# SDtop.net
KiCad netlist of a schematic drawn in Altium Designer
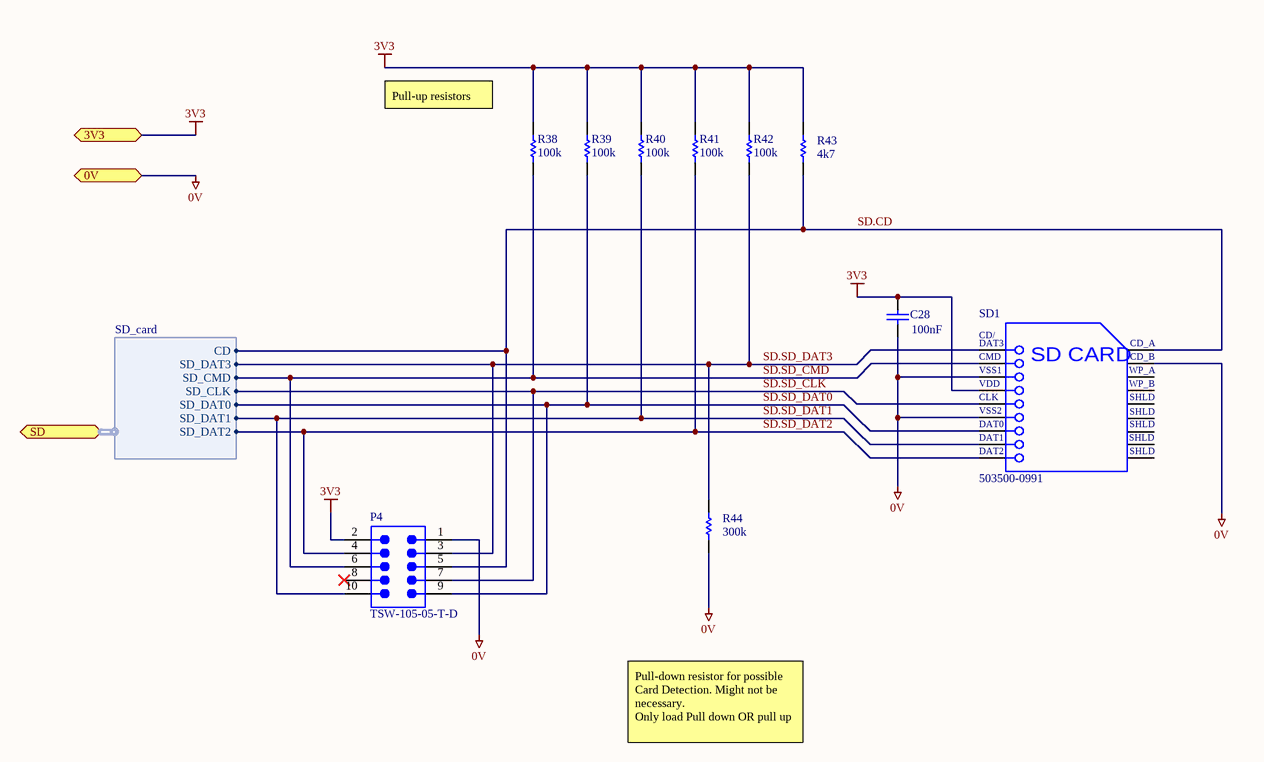
[diagram p0: SDtop.SchDoc]

(export (version "E")
  (design (tool "Eeschema 10.0.6"))
  (components
    (comp (ref "C28")
      (value "100nF")
      (footprint "CAPC0603(1608)100_M")
      (description "CAP 100nF 16V ±5% 0603 (1608 Metric) Thickness 1mm SMD")
      (fields (field (name "TOLERANCE") "Â±5%") (field (name "Comment") "CAP 100nF 16V 0603(1608)"))
      (libsource (lib "Altium Content Vault") (part "CMP-1035-02583-1"))
    )
    (comp (ref "P4")
      (value "TSW-105-05-T-D")
      (footprint "SMTC-TSW-105-05-X-D")
      (fields (field (name "MANUFACTURER") "Samtec"))
      (libsource (lib "Altium Content Vault") (part "SMTC-TSW-105-X-X-D-X"))
    )
    (comp (ref "R38")
      (value "100k")
      (footprint "RESC0603(1608)_N")
      (description "100K 0.1W 1% 0603 (1608 Metric)  SMD")
      (fields (field (name "POWER") "0.1 W") (field (name "TOLERANCE") "1 %"))
      (libsource (lib "Altium Content Vault") (part "CMP-1012-00736-1"))
    )
    (comp (ref "R39")
      (value "100k")
      (footprint "RESC0603(1608)_N")
      (description "100K 0.1W 1% 0603 (1608 Metric)  SMD")
      (fields (field (name "POWER") "0.1 W") (field (name "TOLERANCE") "1 %"))
      (libsource (lib "Altium Content Vault") (part "CMP-1012-00736-1"))
    )
    (comp (ref "R40")
      (value "100k")
      (footprint "RESC0603(1608)_N")
      (description "100K 0.1W 1% 0603 (1608 Metric)  SMD")
      (fields (field (name "POWER") "0.1 W") (field (name "TOLERANCE") "1 %"))
      (libsource (lib "Altium Content Vault") (part "CMP-1012-00736-1"))
    )
    (comp (ref "R41")
      (value "100k")
      (footprint "RESC0603(1608)_N")
      (description "100K 0.1W 1% 0603 (1608 Metric)  SMD")
      (fields (field (name "POWER") "0.1 W") (field (name "TOLERANCE") "1 %"))
      (libsource (lib "Altium Content Vault") (part "CMP-1012-00736-1"))
    )
    (comp (ref "R42")
      (value "100k")
      (footprint "RESC0603(1608)_N")
      (description "100K 0.1W 1% 0603 (1608 Metric)  SMD")
      (fields (field (name "POWER") "0.1 W") (field (name "TOLERANCE") "1 %"))
      (libsource (lib "Altium Content Vault") (part "CMP-1012-00736-1"))
    )
    (comp (ref "R43")
      (value "4k7")
      (footprint "RESC0603(1608)_N")
      (description "4K7 0.1W 1% 0603 (1608 Metric)  SMD")
      (fields (field (name "POWER") "0.1 W") (field (name "TOLERANCE") "1 %"))
      (libsource (lib "Altium Content Vault") (part "CMP-1012-00586-1"))
    )
    (comp (ref "R44")
      (value "300k")
      (footprint "RESC0603(1608)_M")
      (description "300K 0.1W 1% 0603 (1608 Metric)  SMD")
      (fields (field (name "POWER") "0.1 W") (field (name "TOLERANCE") "1 %"))
      (libsource (lib "Altium Content Vault") (part "CMP-1012-00788-1"))
    )
    (comp (ref "SD1")
      (value "503500-0991")
      (footprint "MOLX-503500-0991_V")
      (description "SD and Combo Memory Card Connector, 9 Position Surface Mount, -25 to 85 degC, RoHS, Tape and Reel")
      (libsource (lib "Altium Content Vault") (part "CMP-1676-00006-1"))
    )
  )
  (nets
    (net (code "2") (name "/SD.CD") (class "Default")
      (node (ref "P4") (pin "5") (pinfunction "5_5") (pintype "passive"))
      (node (ref "R43") (pin "1") (pinfunction "1_1") (pintype "passive"))
      (node (ref "SD1") (pin "10") (pinfunction "CD_A_10") (pintype "passive"))
    )
    (net (code "3") (name "/SD.SD_CLK") (class "Default")
      (node (ref "P4") (pin "7") (pinfunction "7_7") (pintype "passive"))
      (node (ref "SD1") (pin "5") (pinfunction "CLK_5") (pintype "passive"))
    )
    (net (code "4") (name "/SD.SD_CMD") (class "Default")
      (node (ref "P4") (pin "6") (pinfunction "6_6") (pintype "passive"))
      (node (ref "R38") (pin "1") (pinfunction "1_1") (pintype "passive"))
      (node (ref "SD1") (pin "2") (pinfunction "CMD_2") (pintype "passive"))
    )
    (net (code "5") (name "/SD.SD_DAT0") (class "Default")
      (node (ref "P4") (pin "9") (pinfunction "9_9") (pintype "passive"))
      (node (ref "R39") (pin "1") (pinfunction "1_1") (pintype "passive"))
      (node (ref "SD1") (pin "7") (pinfunction "DAT0_7") (pintype "passive"))
    )
    (net (code "6") (name "/SD.SD_DAT1") (class "Default")
      (node (ref "P4") (pin "10") (pinfunction "10_10") (pintype "passive"))
      (node (ref "R40") (pin "1") (pinfunction "1_1") (pintype "passive"))
      (node (ref "SD1") (pin "8") (pinfunction "DAT1_8") (pintype "passive"))
    )
    (net (code "7") (name "/SD.SD_DAT2") (class "Default")
      (node (ref "P4") (pin "4") (pinfunction "4_4") (pintype "passive"))
      (node (ref "R41") (pin "1") (pinfunction "1_1") (pintype "passive"))
      (node (ref "SD1") (pin "9") (pinfunction "DAT2_9") (pintype "passive"))
    )
    (net (code "8") (name "/SD.SD_DAT3") (class "Default")
      (node (ref "P4") (pin "3") (pinfunction "3_3") (pintype "passive"))
      (node (ref "R42") (pin "1") (pinfunction "1_1") (pintype "passive"))
      (node (ref "R44") (pin "2") (pinfunction "2_2") (pintype "passive"))
      (node (ref "SD1") (pin "1") (pinfunction "CD/DAT3_1") (pintype "passive"))
    )
    (net (code "10") (name "0V") (class "Default")
      (node (ref "C28") (pin "1") (pinfunction "1_1") (pintype "passive"))
      (node (ref "P4") (pin "1") (pinfunction "1_1") (pintype "passive"))
      (node (ref "R44") (pin "1") (pinfunction "1_1") (pintype "passive"))
      (node (ref "SD1") (pin "11") (pinfunction "CD_B_11") (pintype "passive"))
      (node (ref "SD1") (pin "3") (pinfunction "VSS1_3") (pintype "passive"))
      (node (ref "SD1") (pin "6") (pinfunction "VSS2_6") (pintype "passive"))
    )
    (net (code "11") (name "3V3") (class "Default")
      (node (ref "C28") (pin "2") (pinfunction "2_2") (pintype "passive"))
      (node (ref "P4") (pin "2") (pinfunction "2_2") (pintype "passive"))
      (node (ref "R38") (pin "2") (pinfunction "2_2") (pintype "passive"))
      (node (ref "R39") (pin "2") (pinfunction "2_2") (pintype "passive"))
      (node (ref "R40") (pin "2") (pinfunction "2_2") (pintype "passive"))
      (node (ref "R41") (pin "2") (pinfunction "2_2") (pintype "passive"))
      (node (ref "R42") (pin "2") (pinfunction "2_2") (pintype "passive"))
      (node (ref "R43") (pin "2") (pinfunction "2_2") (pintype "passive"))
      (node (ref "SD1") (pin "4") (pinfunction "VDD_4") (pintype "passive"))
    )
    (net (code "12") (name "unconnected-(P4-Pad8)") (class "Default")
      (node (ref "P4") (pin "8") (pinfunction "8_8") (pintype "passive+no_connect"))
    )
    (net (code "13") (name "unconnected-(SD1-SHLD1-Pad14)") (class "Default")
      (node (ref "SD1") (pin "14") (pinfunction "SHLD1_14") (pintype "passive"))
    )
    (net (code "14") (name "unconnected-(SD1-SHLD2-Pad15)") (class "Default")
      (node (ref "SD1") (pin "15") (pinfunction "SHLD2_15") (pintype "passive"))
    )
    (net (code "15") (name "unconnected-(SD1-SHLD3-Pad16)") (class "Default")
      (node (ref "SD1") (pin "16") (pinfunction "SHLD3_16") (pintype "passive"))
    )
    (net (code "16") (name "unconnected-(SD1-SHLD4-Pad17)") (class "Default")
      (node (ref "SD1") (pin "17") (pinfunction "SHLD4_17") (pintype "passive"))
    )
    (net (code "17") (name "unconnected-(SD1-SHLD5-Pad18)") (class "Default")
      (node (ref "SD1") (pin "18") (pinfunction "SHLD5_18") (pintype "passive"))
    )
    (net (code "18") (name "unconnected-(SD1-WP_A-Pad12)") (class "Default")
      (node (ref "SD1") (pin "12") (pinfunction "WP_A_12") (pintype "passive"))
    )
    (net (code "19") (name "unconnected-(SD1-WP_B-Pad13)") (class "Default")
      (node (ref "SD1") (pin "13") (pinfunction "WP_B_13") (pintype "passive"))
    )
  )
)
